# Power_Suplay.net
KiCad netlist of a schematic drawn in Altium Designer
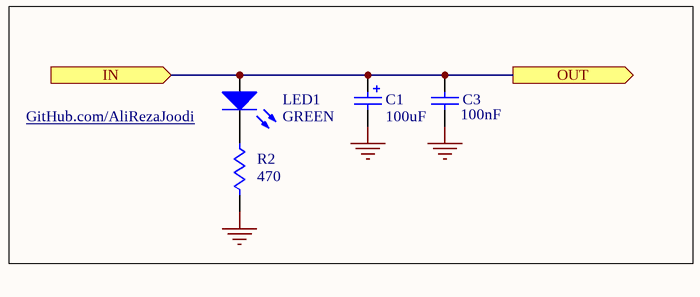
[diagram p0: Power Suplay.SchDoc]

(export (version "E")
  (design (tool "Eeschema 10.0.6"))
  (components
    (comp (ref "C1")
      (value "100uF")
      (footprint "CAPPR2.5-6.3x5")
      (description "Polarized Capacitor (Radial)")
      (fields (field (name "MANUFACTURER") "Generic Components") (field (name "PUBLISHER") "Altium Limited"))
      (libsource (lib "Miscellaneous Devices") (part "Cap Pol1"))
    )
    (comp (ref "C3")
      (value "100nF")
      (footprint "CAPNTO2.54-3.05x1.78A")
      (description "Capacitor")
      (fields (field (name "MANUFACTURER") "Generic Components") (field (name "PUBLISHER") "Altium Limited"))
      (libsource (lib "Miscellaneous Devices") (part "Cap"))
    )
    (comp (ref "LED1")
      (value "GREEN")
      (footprint "LED-5mm_Red")
      (description "Typical INFRARED GaAs LED")
      (fields (field (name "MANUFACTURER") "Generic Components") (field (name "PUBLISHER") "Altium Limited"))
      (libsource (lib "Miscellaneous Devices") (part "LED"))
    )
    (comp (ref "R2")
      (value "470")
      (footprint "AXIAL-0.4")
      (description "Resistor")
      (fields (field (name "MANUFACTURER") "Generic Components") (field (name "PUBLISHER") "Altium Limited"))
      (libsource (lib "Miscellaneous Devices") (part "Res1"))
    )
  )
  (nets
    (net (code "1") (name "/IN") (class "Default")
      (node (ref "C1") (pin "1") (pinfunction "1_1") (pintype "passive"))
      (node (ref "C3") (pin "2") (pinfunction "2_2") (pintype "passive"))
      (node (ref "LED1") (pin "1") (pinfunction "A_1") (pintype "passive"))
    )
    (net (code "2") (name "GND") (class "Default")
      (node (ref "C1") (pin "2") (pinfunction "2_2") (pintype "passive"))
      (node (ref "C3") (pin "1") (pinfunction "1_1") (pintype "passive"))
      (node (ref "R2") (pin "2") (pinfunction "2_2") (pintype "passive"))
    )
    (net (code "3") (name "Net-(LED1-K)") (class "Default")
      (node (ref "LED1") (pin "2") (pinfunction "K_2") (pintype "passive"))
      (node (ref "R2") (pin "1") (pinfunction "1_1") (pintype "passive"))
    )
  )
)
